# Dual_Flowmeter.net
KiCad netlist of a schematic drawn in Altium Designer
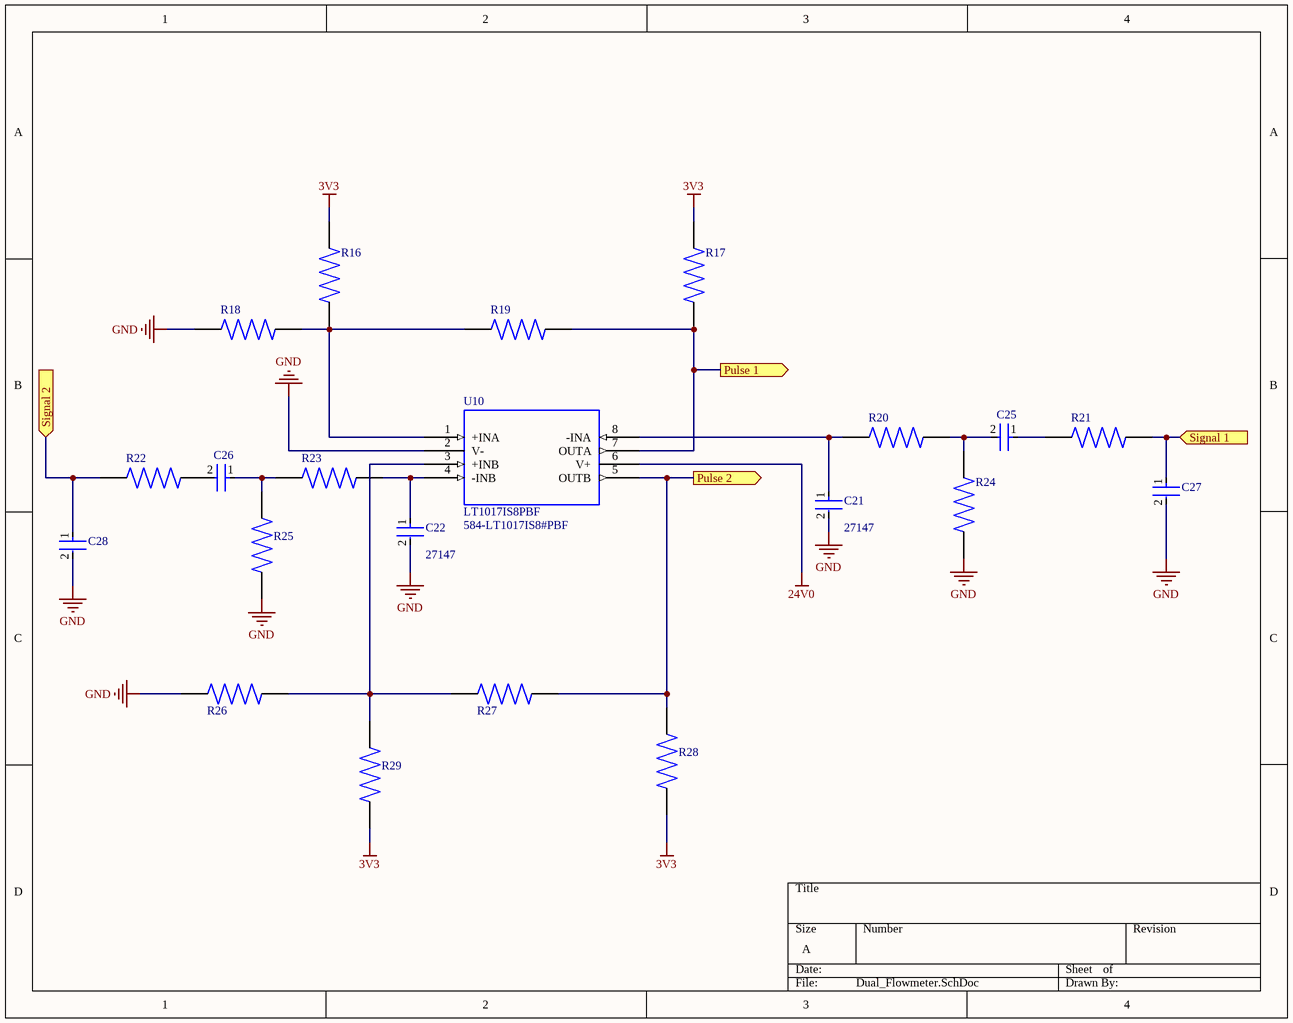
[diagram p0: Dual_Flowmeter.SchDoc]

(export (version "E")
  (design (tool "Eeschema 10.0.6"))
  (components
    (comp (ref "C21")
      (value "C1206C222K5RACTU")
      (footprint "FP-C1206C-EB-IPC_A")
      (description "CAPACITOR SMD Multilayer Ceramic MLCC 1206 Case 2200pF ±10% 50Vdc X7R Dielectric -55°C~+125°C T/R")
      (fields
        (field (name "MANUFACTURER") "KEMET")
        (field (name "TOLERANCE") "10%")
        (field (name "STOCK 1") "27147")
      )
      (libsource (lib "Replacements") (part "C1206C222K5RACTU"))
    )
    (comp (ref "C22")
      (value "C1206C222K5RACTU")
      (footprint "FP-C1206C-EB-IPC_A")
      (description "CAPACITOR SMD Multilayer Ceramic MLCC 1206 Case 2200pF ±10% 50Vdc X7R Dielectric -55°C~+125°C T/R")
      (fields
        (field (name "MANUFACTURER") "KEMET")
        (field (name "TOLERANCE") "10%")
        (field (name "STOCK 1") "27147")
      )
      (libsource (lib "Replacements") (part "C1206C222K5RACTU"))
    )
    (comp (ref "C25")
      (value "GRM21BR61E106KA73L")
      (footprint "FP-GRM21B-0_15-IPC_A")
      (description "0805 10 uF 25 V ±10% Tolerance X5R SMT Multilayer Ceramic Capacitor")
      (fields (field (name "MANUFACTURER") "Murata") (field (name "TOLERANCE") "10%"))
      (libsource (lib "Replacements") (part "GRM21BR61E106KA73L"))
    )
    (comp (ref "C26")
      (value "GRM21BR61E106KA73L")
      (footprint "FP-GRM21B-0_15-IPC_A")
      (description "0805 10 uF 25 V ±10% Tolerance X5R SMT Multilayer Ceramic Capacitor")
      (fields (field (name "MANUFACTURER") "Murata") (field (name "TOLERANCE") "10%"))
      (libsource (lib "Replacements") (part "GRM21BR61E106KA73L"))
    )
    (comp (ref "C27")
      (value "GRM21BR61E106KA73L")
      (footprint "FP-GRM21B-0_15-IPC_A")
      (description "0805 10 uF 25 V ±10% Tolerance X5R SMT Multilayer Ceramic Capacitor")
      (fields (field (name "MANUFACTURER") "Murata") (field (name "TOLERANCE") "10%"))
      (libsource (lib "Replacements") (part "GRM21BR61E106KA73L"))
    )
    (comp (ref "C28")
      (value "GRM21BR61E106KA73L")
      (footprint "FP-GRM21B-0_15-IPC_A")
      (description "0805 10 uF 25 V ±10% Tolerance X5R SMT Multilayer Ceramic Capacitor")
      (fields (field (name "MANUFACTURER") "Murata") (field (name "TOLERANCE") "10%"))
      (libsource (lib "Replacements") (part "GRM21BR61E106KA73L"))
    )
    (comp (ref "R16")
      (value "RC1206JR-07100KL")
      (footprint "RESC3116X65N")
      (description "Carbon film resistor 100 kâ„¦ SMD 1206 0.25 W 5 % 200 ppm Yageo RC1206JR-07100KL 1 pc(s)")
      (libsource (lib "100K_Res_RC1206JR-07100KL") (part "RC1206JR-07100KL"))
    )
    (comp (ref "R17")
      (value "RC0402FR-073K3P")
      (footprint "RESC1005X40N")
      (description "Chip Resistor Surface Mount")
      (libsource (lib "3.3K_Res_RC0402FR-073K3P") (part "RC0402FR-073K3P"))
    )
    (comp (ref "R18")
      (value "CRS2010AFX-1001ELF")
      (footprint "RESC5025X70N")
      (libsource (lib "1K_Res_CRS2010AFX-1001ELF") (part "CRS2010AFX-1001ELF"))
    )
    (comp (ref "R19")
      (value "ERJS03F1004V")
      (footprint "RES_ERJS03F1004V")
      (description "Res Thick Film 0603 1M Ohm 1% 0.1W(1/10W) Â±100ppm/Â°C Sulfur Resistant Pad SMD Automotive T/R")
      (fields (field (name "MP") "ERJ-S03F1004V") (field (name "MF") "Panasonic"))
      (libsource (lib "1M_Res_ERJS03F1004V") (part "ERJS03F1004V"))
    )
    (comp (ref "R20")
      (value "CR0603-JW-512ELF")
      (footprint "RESC1608X55N")
      (description "Resistor Thick Film 0603 5.1k Ohm 5% 1/10 Watt Â±200ppm Â°C Surface Mount Paper Tape On Plastic Reel")
      (libsource (lib "5.1K_Res_CR0603-JW-512ELF") (part "CR0603-JW-512ELF"))
    )
    (comp (ref "R21")
      (value "RT0603DRE072K21L")
      (footprint "RESC1608X55N")
      (description "RES SMD 2.21KOHM 0.5% 1/10W 0603")
      (libsource (lib "2.21K_Res_RT0603DRE072K21L") (part "RT0603DRE072K21L"))
    )
    (comp (ref "R22")
      (value "RT0603DRE072K21L")
      (footprint "RESC1608X55N")
      (description "RES SMD 2.21KOHM 0.5% 1/10W 0603")
      (libsource (lib "2.21K_Res_RT0603DRE072K21L") (part "RT0603DRE072K21L"))
    )
    (comp (ref "R23")
      (value "CR0603-JW-512ELF")
      (footprint "RESC1608X55N")
      (description "Resistor Thick Film 0603 5.1k Ohm 5% 1/10 Watt Â±200ppm Â°C Surface Mount Paper Tape On Plastic Reel")
      (libsource (lib "5.1K_Res_CR0603-JW-512ELF") (part "CR0603-JW-512ELF"))
    )
    (comp (ref "R24")
      (value "CR0603-JW-512ELF")
      (footprint "RESC1608X55N")
      (description "Resistor Thick Film 0603 5.1k Ohm 5% 1/10 Watt Â±200ppm Â°C Surface Mount Paper Tape On Plastic Reel")
      (libsource (lib "5.1K_Res_CR0603-JW-512ELF") (part "CR0603-JW-512ELF"))
    )
    (comp (ref "R25")
      (value "CR0603-JW-512ELF")
      (footprint "RESC1608X55N")
      (description "Resistor Thick Film 0603 5.1k Ohm 5% 1/10 Watt Â±200ppm Â°C Surface Mount Paper Tape On Plastic Reel")
      (libsource (lib "5.1K_Res_CR0603-JW-512ELF") (part "CR0603-JW-512ELF"))
    )
    (comp (ref "R26")
      (value "CRS2010AFX-1001ELF")
      (footprint "RESC5025X70N")
      (libsource (lib "1K_Res_CRS2010AFX-1001ELF") (part "CRS2010AFX-1001ELF"))
    )
    (comp (ref "R27")
      (value "ERJS03F1004V")
      (footprint "RES_ERJS03F1004V")
      (description "Res Thick Film 0603 1M Ohm 1% 0.1W(1/10W) Â±100ppm/Â°C Sulfur Resistant Pad SMD Automotive T/R")
      (fields (field (name "MP") "ERJ-S03F1004V") (field (name "MF") "Panasonic"))
      (libsource (lib "1M_Res_ERJS03F1004V") (part "ERJS03F1004V"))
    )
    (comp (ref "R28")
      (value "RC0402FR-073K3P")
      (footprint "RESC1005X40N")
      (description "Chip Resistor Surface Mount")
      (libsource (lib "3.3K_Res_RC0402FR-073K3P") (part "RC0402FR-073K3P"))
    )
    (comp (ref "R29")
      (value "RC1206JR-07100KL")
      (footprint "RESC3116X65N")
      (description "Carbon film resistor 100 kâ„¦ SMD 1206 0.25 W 5 % 200 ppm Yageo RC1206JR-07100KL 1 pc(s)")
      (libsource (lib "100K_Res_RC1206JR-07100KL") (part "RC1206JR-07100KL"))
    )
    (comp (ref "U10")
      (value "LT1017IS8PBF")
      (footprint "SO-8_S")
      (description "Comparator General Purpose Pull Up 8-SOIC")
      (fields
        (field (name "MF") "Analog Devices")
        (field (name "MP") "LT1017IS8#PBF")
        (field (name "SUPPLIER PART NUMBER 1") "584-LT1017IS8#PBF")
      )
      (libsource (lib "Comparator_LT1017IS8PBF") (part "LT1017IS8PBF"))
    )
  )
  (nets
    (net (code "1") (name "/Pulse 1") (class "Default")
      (node (ref "R17") (pin "2") (pinfunction "2_2") (pintype "passive"))
      (node (ref "R19") (pin "2") (pinfunction "2_2") (pintype "passive"))
      (node (ref "U10") (pin "7") (pinfunction "OUTA_7") (pintype "output"))
    )
    (net (code "2") (name "/Pulse 2") (class "Default")
      (node (ref "R27") (pin "1") (pinfunction "1_1") (pintype "passive"))
      (node (ref "R28") (pin "2") (pinfunction "2_2") (pintype "passive"))
      (node (ref "U10") (pin "5") (pinfunction "OUTB_5") (pintype "output"))
    )
    (net (code "3") (name "/Signal 1") (class "Default")
      (node (ref "C27") (pin "1") (pinfunction "1_1") (pintype "passive"))
      (node (ref "R21") (pin "2") (pinfunction "2_2") (pintype "passive"))
    )
    (net (code "4") (name "/Signal 2") (class "Default")
      (node (ref "C28") (pin "1") (pinfunction "1_1") (pintype "passive"))
      (node (ref "R22") (pin "1") (pinfunction "1_1") (pintype "passive"))
    )
    (net (code "5") (name "3V3") (class "Default")
      (node (ref "R16") (pin "1") (pinfunction "1_1") (pintype "passive"))
      (node (ref "R17") (pin "1") (pinfunction "1_1") (pintype "passive"))
      (node (ref "R28") (pin "1") (pinfunction "1_1") (pintype "passive"))
      (node (ref "R29") (pin "1") (pinfunction "1_1") (pintype "passive"))
    )
    (net (code "6") (name "24V0") (class "Default")
      (node (ref "U10") (pin "6") (pinfunction "V+_6") (pintype "power_in"))
    )
    (net (code "7") (name "GND") (class "Default")
      (node (ref "C21") (pin "2") (pinfunction "2_2") (pintype "passive"))
      (node (ref "C22") (pin "2") (pinfunction "2_2") (pintype "passive"))
      (node (ref "C27") (pin "2") (pinfunction "2_2") (pintype "passive"))
      (node (ref "C28") (pin "2") (pinfunction "2_2") (pintype "passive"))
      (node (ref "R18") (pin "1") (pinfunction "1_1") (pintype "passive"))
      (node (ref "R24") (pin "2") (pinfunction "2_2") (pintype "passive"))
      (node (ref "R25") (pin "2") (pinfunction "2_2") (pintype "passive"))
      (node (ref "R26") (pin "2") (pinfunction "2_2") (pintype "passive"))
      (node (ref "U10") (pin "2") (pinfunction "V-_2") (pintype "power_in"))
    )
    (net (code "8") (name "Net-(C25-Pad1)") (class "Default")
      (node (ref "C25") (pin "1") (pinfunction "1_1") (pintype "passive"))
      (node (ref "R21") (pin "1") (pinfunction "1_1") (pintype "passive"))
    )
    (net (code "9") (name "Net-(C25-Pad2)") (class "Default")
      (node (ref "C25") (pin "2") (pinfunction "2_2") (pintype "passive"))
      (node (ref "R20") (pin "2") (pinfunction "2_2") (pintype "passive"))
      (node (ref "R24") (pin "1") (pinfunction "1_1") (pintype "passive"))
    )
    (net (code "10") (name "Net-(C26-Pad1)") (class "Default")
      (node (ref "C26") (pin "1") (pinfunction "1_1") (pintype "passive"))
      (node (ref "R23") (pin "1") (pinfunction "1_1") (pintype "passive"))
      (node (ref "R25") (pin "1") (pinfunction "1_1") (pintype "passive"))
    )
    (net (code "11") (name "Net-(C26-Pad2)") (class "Default")
      (node (ref "C26") (pin "2") (pinfunction "2_2") (pintype "passive"))
      (node (ref "R22") (pin "2") (pinfunction "2_2") (pintype "passive"))
    )
    (net (code "12") (name "Net-(U10-+INA)") (class "Default")
      (node (ref "R16") (pin "2") (pinfunction "2_2") (pintype "passive"))
      (node (ref "R18") (pin "2") (pinfunction "2_2") (pintype "passive"))
      (node (ref "R19") (pin "1") (pinfunction "1_1") (pintype "passive"))
      (node (ref "U10") (pin "1") (pinfunction "+INA_1") (pintype "input"))
    )
    (net (code "13") (name "Net-(U10-+INB)") (class "Default")
      (node (ref "R26") (pin "1") (pinfunction "1_1") (pintype "passive"))
      (node (ref "R27") (pin "2") (pinfunction "2_2") (pintype "passive"))
      (node (ref "R29") (pin "2") (pinfunction "2_2") (pintype "passive"))
      (node (ref "U10") (pin "3") (pinfunction "+INB_3") (pintype "input"))
    )
    (net (code "14") (name "Net-(U10--INA)") (class "Default")
      (node (ref "C21") (pin "1") (pinfunction "1_1") (pintype "passive"))
      (node (ref "R20") (pin "1") (pinfunction "1_1") (pintype "passive"))
      (node (ref "U10") (pin "8") (pinfunction "-INA_8") (pintype "input"))
    )
    (net (code "15") (name "Net-(U10--INB)") (class "Default")
      (node (ref "C22") (pin "1") (pinfunction "1_1") (pintype "passive"))
      (node (ref "R23") (pin "2") (pinfunction "2_2") (pintype "passive"))
      (node (ref "U10") (pin "4") (pinfunction "-INB_4") (pintype "input"))
    )
  )
)
